# Hall_Input.net
KiCad netlist of a schematic drawn in Altium Designer
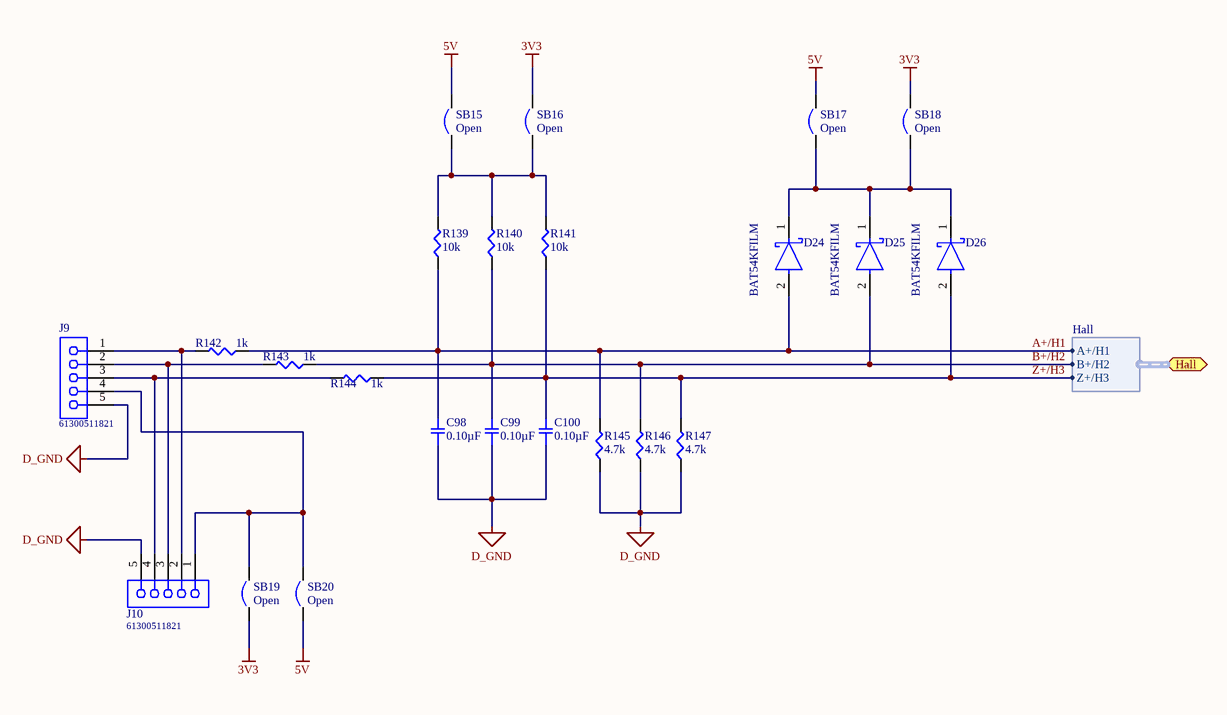
[diagram p0: Hall_Input.SchDoc]

(export (version "E")
  (design (tool "Eeschema 10.0.6"))
  (components
    (comp (ref "C98")
      (value "0.10µF")
      (footprint "SMD-0805C")
      (description "CAP CER 0.1UF 50V X7R 0805")
      (fields
        (field (name "DIGI-KEY PART NUMBER") "490-11955-1-ND")
        (field (name "PART NUMBER") "GCD21BR71H104KA01L")
      )
      (libsource (lib "capacitor_murata_0805") (part "GCD21BR71H104KA01L"))
    )
    (comp (ref "C99")
      (value "0.10µF")
      (footprint "SMD-0805C")
      (description "CAP CER 0.1UF 50V X7R 0805")
      (fields
        (field (name "DIGI-KEY PART NUMBER") "490-11955-1-ND")
        (field (name "PART NUMBER") "GCD21BR71H104KA01L")
      )
      (libsource (lib "capacitor_murata_0805") (part "GCD21BR71H104KA01L"))
    )
    (comp (ref "C100")
      (value "0.10µF")
      (footprint "SMD-0805C")
      (description "CAP CER 0.1UF 50V X7R 0805")
      (fields
        (field (name "DIGI-KEY PART NUMBER") "490-11955-1-ND")
        (field (name "PART NUMBER") "GCD21BR71H104KA01L")
      )
      (libsource (lib "capacitor_murata_0805") (part "GCD21BR71H104KA01L"))
    )
    (comp (ref "D24")
      (value "BAT54KFILM")
      (footprint "FP-SOD-523-MFG")
      (description "DIODE SCHOTTKY 40V 300MA SOD523")
      (fields
        (field (name "OCTOPART") "https://octopart.com/bat54kfilm-stmicroelectronics-39618022")
        (field (name "MANUFACTURER") "STMicroelectronics")
      )
      (libsource (lib "Altium Content Vault") (part "1d6ec82d83fb6aee721767c19dac4b9"))
    )
    (comp (ref "D25")
      (value "BAT54KFILM")
      (footprint "FP-SOD-523-MFG")
      (description "DIODE SCHOTTKY 40V 300MA SOD523")
      (fields
        (field (name "OCTOPART") "https://octopart.com/bat54kfilm-stmicroelectronics-39618022")
        (field (name "MANUFACTURER") "STMicroelectronics")
      )
      (libsource (lib "Altium Content Vault") (part "1d6ec82d83fb6aee721767c19dac4b9"))
    )
    (comp (ref "D26")
      (value "BAT54KFILM")
      (footprint "FP-SOD-523-MFG")
      (description "DIODE SCHOTTKY 40V 300MA SOD523")
      (fields
        (field (name "OCTOPART") "https://octopart.com/bat54kfilm-stmicroelectronics-39618022")
        (field (name "MANUFACTURER") "STMicroelectronics")
      )
      (libsource (lib "Altium Content Vault") (part "1d6ec82d83fb6aee721767c19dac4b9"))
    )
    (comp (ref "J9")
      (value "61300511821")
      (footprint "61300511821")
      (description "WR-PHD Socket Header, THT, pitch 2.54mm, Single Row, Vertical, 5pin")
      (fields (field (name "PUBLISHER") "Wurth Elektronik"))
      (libsource (lib "o155175v243 Altium_WR-PHD (rev19a)") (part "61300511821"))
    )
    (comp (ref "J10")
      (value "61300511821")
      (footprint "61300511821")
      (description "WR-PHD Socket Header, THT, pitch 2.54mm, Single Row, Vertical, 5pin")
      (fields (field (name "PUBLISHER") "Wurth Elektronik"))
      (libsource (lib "o155175v243 Altium_WR-PHD (rev19a)") (part "61300511821"))
    )
    (comp (ref "R139")
      (value "10k")
      (footprint "SMD-0603-RES")
      (description "RES SMD 10K OHM 1% 1/10W 0603")
      (fields
        (field (name "PART NUMBER") "ERJ-3EKF1002V")
        (field (name "DIGI-KEY PART NUMBER") "P10.0KHCT-ND")
      )
      (libsource (lib "Panasonic_ERJ_0603") (part "ERJ-3EKF1002V"))
    )
    (comp (ref "R140")
      (value "10k")
      (footprint "SMD-0603-RES")
      (description "RES SMD 10K OHM 1% 1/10W 0603")
      (fields
        (field (name "PART NUMBER") "ERJ-3EKF1002V")
        (field (name "DIGI-KEY PART NUMBER") "P10.0KHCT-ND")
      )
      (libsource (lib "Panasonic_ERJ_0603") (part "ERJ-3EKF1002V"))
    )
    (comp (ref "R141")
      (value "10k")
      (footprint "SMD-0603-RES")
      (description "RES SMD 10K OHM 1% 1/10W 0603")
      (fields
        (field (name "PART NUMBER") "ERJ-3EKF1002V")
        (field (name "DIGI-KEY PART NUMBER") "P10.0KHCT-ND")
      )
      (libsource (lib "Panasonic_ERJ_0603") (part "ERJ-3EKF1002V"))
    )
    (comp (ref "R142")
      (value "1k")
      (footprint "SMD-0603-RES")
      (description "RES SMD 1K OHM 1% 1/10W 0603")
      (fields
        (field (name "PART NUMBER") "ERJ-3EKF1001V")
        (field (name "DIGI-KEY PART NUMBER") "P1.00KHCT-ND")
      )
      (libsource (lib "Panasonic_ERJ_0603") (part "ERJ-3EKF1001V"))
    )
    (comp (ref "R143")
      (value "1k")
      (footprint "SMD-0603-RES")
      (description "RES SMD 1K OHM 1% 1/10W 0603")
      (fields
        (field (name "PART NUMBER") "ERJ-3EKF1001V")
        (field (name "DIGI-KEY PART NUMBER") "P1.00KHCT-ND")
      )
      (libsource (lib "Panasonic_ERJ_0603") (part "ERJ-3EKF1001V"))
    )
    (comp (ref "R144")
      (value "1k")
      (footprint "SMD-0603-RES")
      (description "RES SMD 1K OHM 1% 1/10W 0603")
      (fields
        (field (name "PART NUMBER") "ERJ-3EKF1001V")
        (field (name "DIGI-KEY PART NUMBER") "P1.00KHCT-ND")
      )
      (libsource (lib "Panasonic_ERJ_0603") (part "ERJ-3EKF1001V"))
    )
    (comp (ref "R145")
      (value "4.7k")
      (footprint "SMD-0603-RES")
      (description "RES SMD 4.7K OHM 5% 1/10W 0603")
      (fields
        (field (name "PART NUMBER") "ERJ-3GEYJ472V")
        (field (name "DIGI-KEY PART NUMBER") "P4.7KGCT-ND")
      )
      (libsource (lib "Panasonic_ERJ_0603") (part "ERJ-3GEYJ472V"))
    )
    (comp (ref "R146")
      (value "4.7k")
      (footprint "SMD-0603-RES")
      (description "RES SMD 4.7K OHM 5% 1/10W 0603")
      (fields
        (field (name "PART NUMBER") "ERJ-3GEYJ472V")
        (field (name "DIGI-KEY PART NUMBER") "P4.7KGCT-ND")
      )
      (libsource (lib "Panasonic_ERJ_0603") (part "ERJ-3GEYJ472V"))
    )
    (comp (ref "R147")
      (value "4.7k")
      (footprint "SMD-0603-RES")
      (description "RES SMD 4.7K OHM 5% 1/10W 0603")
      (fields
        (field (name "PART NUMBER") "ERJ-3GEYJ472V")
        (field (name "DIGI-KEY PART NUMBER") "P4.7KGCT-ND")
      )
      (libsource (lib "Panasonic_ERJ_0603") (part "ERJ-3GEYJ472V"))
    )
    (comp (ref "SB15")
      (value "Open")
      (footprint "Solder Bridge - HP - SQ")
      (description "Circuit Breaker")
      (fields (field (name "PUBLISHER") "Altium Limited"))
      (libsource (lib "NUCLEOG431RB-Custom-IN-A2212") (part "Solder Bridge"))
    )
    (comp (ref "SB16")
      (value "Open")
      (footprint "Solder Bridge - HP - SQ")
      (description "Circuit Breaker")
      (fields (field (name "PUBLISHER") "Altium Limited"))
      (libsource (lib "NUCLEOG431RB-Custom-IN-A2212") (part "Solder Bridge"))
    )
    (comp (ref "SB17")
      (value "Open")
      (footprint "Solder Bridge - HP - SQ")
      (description "Circuit Breaker")
      (fields (field (name "PUBLISHER") "Altium Limited"))
      (libsource (lib "NUCLEOG431RB-Custom-IN-A2212") (part "Solder Bridge"))
    )
    (comp (ref "SB18")
      (value "Open")
      (footprint "Solder Bridge - HP - SQ")
      (description "Circuit Breaker")
      (fields (field (name "PUBLISHER") "Altium Limited"))
      (libsource (lib "NUCLEOG431RB-Custom-IN-A2212") (part "Solder Bridge"))
    )
    (comp (ref "SB19")
      (value "Open")
      (footprint "Solder Bridge - HP - SQ")
      (description "Circuit Breaker")
      (fields (field (name "PUBLISHER") "Altium Limited"))
      (libsource (lib "NUCLEOG431RB-Custom-IN-A2212") (part "Solder Bridge"))
    )
    (comp (ref "SB20")
      (value "Open")
      (footprint "Solder Bridge - HP - SQ")
      (description "Circuit Breaker")
      (fields (field (name "PUBLISHER") "Altium Limited"))
      (libsource (lib "NUCLEOG431RB-Custom-IN-A2212") (part "Solder Bridge"))
    )
  )
  (nets
    (net (code "2") (name "/A+{slash}H1") (class "Default")
      (node (ref "C98") (pin "2") (pinfunction "2_2") (pintype "passive"))
      (node (ref "D24") (pin "2") (pinfunction "A_2") (pintype "passive"))
      (node (ref "R139") (pin "1") (pinfunction "1_1") (pintype "passive"))
      (node (ref "R142") (pin "1") (pinfunction "1_1") (pintype "passive"))
      (node (ref "R145") (pin "2") (pinfunction "2_2") (pintype "passive"))
    )
    (net (code "3") (name "/B+{slash}H2") (class "Default")
      (node (ref "C99") (pin "2") (pinfunction "2_2") (pintype "passive"))
      (node (ref "D25") (pin "2") (pinfunction "A_2") (pintype "passive"))
      (node (ref "R140") (pin "1") (pinfunction "1_1") (pintype "passive"))
      (node (ref "R143") (pin "1") (pinfunction "1_1") (pintype "passive"))
      (node (ref "R146") (pin "2") (pinfunction "2_2") (pintype "passive"))
    )
    (net (code "4") (name "/Z+{slash}H3") (class "Default")
      (node (ref "C100") (pin "2") (pinfunction "2_2") (pintype "passive"))
      (node (ref "D26") (pin "2") (pinfunction "A_2") (pintype "passive"))
      (node (ref "R141") (pin "1") (pinfunction "1_1") (pintype "passive"))
      (node (ref "R144") (pin "1") (pinfunction "1_1") (pintype "passive"))
      (node (ref "R147") (pin "2") (pinfunction "2_2") (pintype "passive"))
    )
    (net (code "6") (name "3V3") (class "Default")
      (node (ref "SB16") (pin "2") (pinfunction "2_2") (pintype "passive"))
      (node (ref "SB18") (pin "2") (pinfunction "2_2") (pintype "passive"))
      (node (ref "SB19") (pin "1") (pinfunction "1_1") (pintype "passive"))
    )
    (net (code "7") (name "5V") (class "Default")
      (node (ref "SB15") (pin "2") (pinfunction "2_2") (pintype "passive"))
      (node (ref "SB17") (pin "2") (pinfunction "2_2") (pintype "passive"))
      (node (ref "SB20") (pin "1") (pinfunction "1_1") (pintype "passive"))
    )
    (net (code "8") (name "D_GND") (class "Default")
      (node (ref "C100") (pin "1") (pinfunction "1_1") (pintype "passive"))
      (node (ref "C98") (pin "1") (pinfunction "1_1") (pintype "passive"))
      (node (ref "C99") (pin "1") (pinfunction "1_1") (pintype "passive"))
      (node (ref "J10") (pin "5") (pinfunction "5_5") (pintype "passive"))
      (node (ref "J9") (pin "5") (pinfunction "5_5") (pintype "passive"))
      (node (ref "R145") (pin "1") (pinfunction "1_1") (pintype "passive"))
      (node (ref "R146") (pin "1") (pinfunction "1_1") (pintype "passive"))
      (node (ref "R147") (pin "1") (pinfunction "1_1") (pintype "passive"))
    )
    (net (code "9") (name "Net-(D24-C)") (class "Default")
      (node (ref "D24") (pin "1") (pinfunction "C_1") (pintype "passive"))
      (node (ref "D25") (pin "1") (pinfunction "C_1") (pintype "passive"))
      (node (ref "D26") (pin "1") (pinfunction "C_1") (pintype "passive"))
      (node (ref "SB17") (pin "1") (pinfunction "1_1") (pintype "passive"))
      (node (ref "SB18") (pin "1") (pinfunction "1_1") (pintype "passive"))
    )
    (net (code "10") (name "Net-(J10-Pad1)") (class "Default")
      (node (ref "J10") (pin "1") (pinfunction "1_1") (pintype "passive"))
      (node (ref "J9") (pin "4") (pinfunction "4_4") (pintype "passive"))
      (node (ref "SB19") (pin "2") (pinfunction "2_2") (pintype "passive"))
      (node (ref "SB20") (pin "2") (pinfunction "2_2") (pintype "passive"))
    )
    (net (code "11") (name "Net-(J10-Pad2)") (class "Default")
      (node (ref "J10") (pin "2") (pinfunction "2_2") (pintype "passive"))
      (node (ref "J9") (pin "1") (pinfunction "1_1") (pintype "passive"))
      (node (ref "R142") (pin "2") (pinfunction "2_2") (pintype "passive"))
    )
    (net (code "12") (name "Net-(J10-Pad3)") (class "Default")
      (node (ref "J10") (pin "3") (pinfunction "3_3") (pintype "passive"))
      (node (ref "J9") (pin "2") (pinfunction "2_2") (pintype "passive"))
      (node (ref "R143") (pin "2") (pinfunction "2_2") (pintype "passive"))
    )
    (net (code "13") (name "Net-(J10-Pad4)") (class "Default")
      (node (ref "J10") (pin "4") (pinfunction "4_4") (pintype "passive"))
      (node (ref "J9") (pin "3") (pinfunction "3_3") (pintype "passive"))
      (node (ref "R144") (pin "2") (pinfunction "2_2") (pintype "passive"))
    )
    (net (code "14") (name "Net-(R139-Pad2)") (class "Default")
      (node (ref "R139") (pin "2") (pinfunction "2_2") (pintype "passive"))
      (node (ref "R140") (pin "2") (pinfunction "2_2") (pintype "passive"))
      (node (ref "R141") (pin "2") (pinfunction "2_2") (pintype "passive"))
      (node (ref "SB15") (pin "1") (pinfunction "1_1") (pintype "passive"))
      (node (ref "SB16") (pin "1") (pinfunction "1_1") (pintype "passive"))
    )
  )
)
